# EXP_TMS9918A_V1.net
KiCad netlist of a schematic drawn in EAGLE
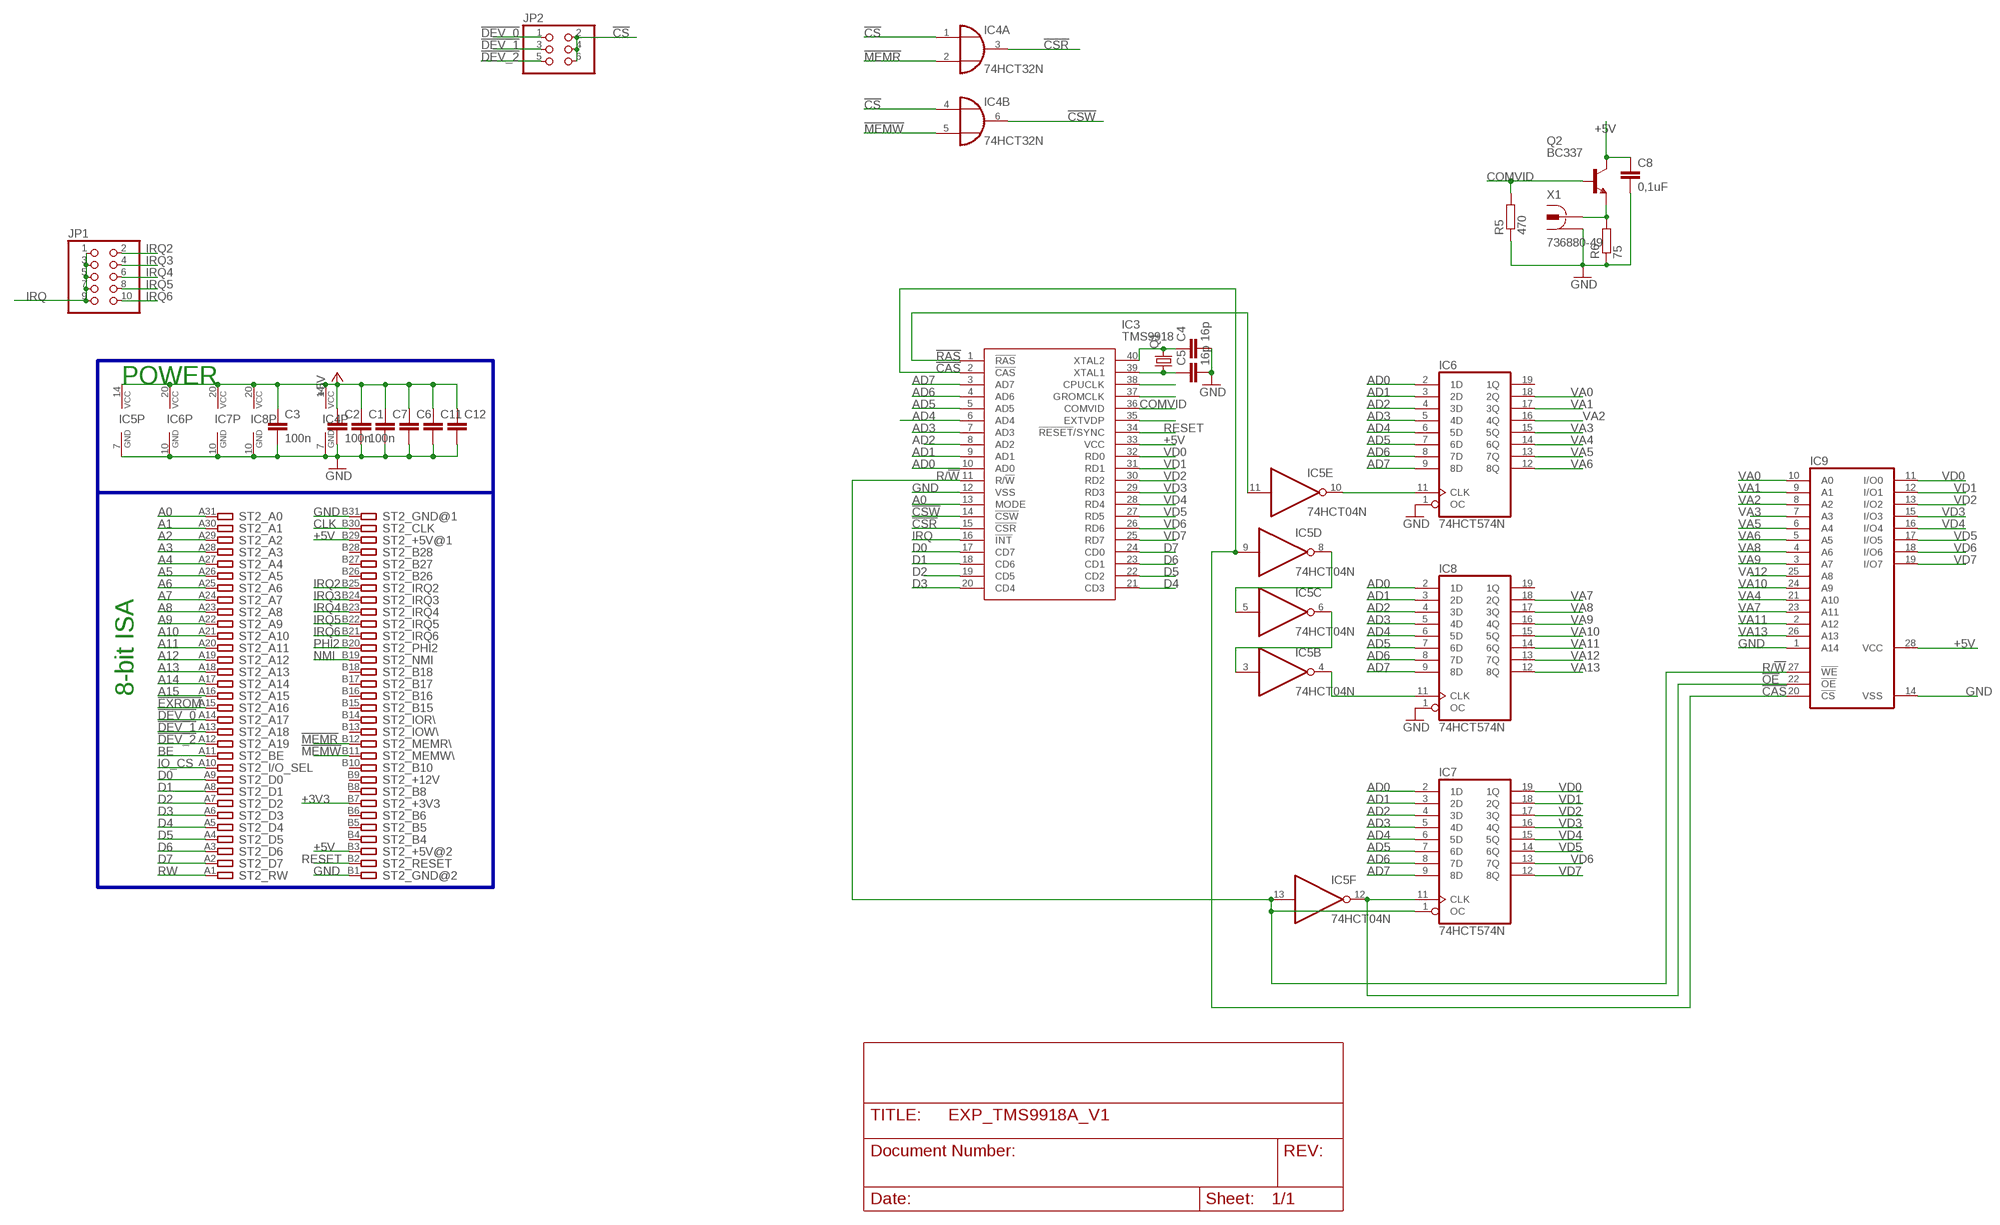
[diagram p0: schematic, sheet 1]

(export (version "E")
  (design (tool "Eeschema 10.0.6"))
  (components
    (comp (ref "C1")
      (value "100n")
      (footprint "eagle-import:C050-025X075")
      (libsource (lib "eagle-import") (part "C-EU050-025X075"))
    )
    (comp (ref "C2")
      (value "100n")
      (footprint "eagle-import:C050-025X075")
      (libsource (lib "eagle-import") (part "C-EU050-025X075"))
    )
    (comp (ref "C3")
      (value "100n")
      (footprint "eagle-import:C050-025X075")
      (libsource (lib "eagle-import") (part "C-EU050-025X075"))
    )
    (comp (ref "C4")
      (value "16p")
      (footprint "eagle-import:C050-024X044")
      (libsource (lib "eagle-import") (part "rcl_334_C-EU050-024X044"))
    )
    (comp (ref "C5")
      (value "16p")
      (footprint "eagle-import:C050-024X044")
      (libsource (lib "eagle-import") (part "rcl_334_C-EU050-024X044"))
    )
    (comp (ref "C6")
      (value "C-EU050-035X075")
      (footprint "eagle-import:C050-035X075")
      (libsource (lib "eagle-import") (part "rcl_334_C-EU050-035X075"))
    )
    (comp (ref "C7")
      (value "C-EU050-035X075")
      (footprint "eagle-import:C050-035X075")
      (libsource (lib "eagle-import") (part "rcl_334_C-EU050-035X075"))
    )
    (comp (ref "C8")
      (value "0,1uF")
      (footprint "eagle-import:C050-024X044")
      (libsource (lib "eagle-import") (part "rcl_334_C-EU050-024X044"))
    )
    (comp (ref "C11")
      (value "C-EU050-035X075")
      (footprint "eagle-import:C050-035X075")
      (libsource (lib "eagle-import") (part "rcl_334_C-EU050-035X075"))
    )
    (comp (ref "C12")
      (value "C-EU050-035X075")
      (footprint "eagle-import:C050-035X075")
      (libsource (lib "eagle-import") (part "rcl_334_C-EU050-035X075"))
    )
    (comp (ref "IC3")
      (value "TMS9918")
      (footprint "eagle-import:DIP1524W53P254L5310H508Q40N")
      (libsource (lib "eagle-import") (part "TMS9918"))
    )
    (comp (ref "IC4")
      (value "74HCT32N")
      (footprint "eagle-import:DIL14")
      (libsource (lib "eagle-import") (part "7432NHCT"))
    )
    (comp (ref "IC5")
      (value "74HCT04N")
      (footprint "eagle-import:DIL14")
      (libsource (lib "eagle-import") (part "7404NHCT"))
    )
    (comp (ref "IC6")
      (value "74HCT574N")
      (footprint "eagle-import:DIL20")
      (libsource (lib "eagle-import") (part "74574NHCT"))
    )
    (comp (ref "IC7")
      (value "74HCT574N")
      (footprint "eagle-import:DIL20")
      (libsource (lib "eagle-import") (part "74574NHCT"))
    )
    (comp (ref "IC8")
      (value "74HCT574N")
      (footprint "eagle-import:DIL20")
      (libsource (lib "eagle-import") (part "74574NHCT"))
    )
    (comp (ref "IC9")
      (value "62256P")
      (footprint "eagle-import:DIL28-6")
      (libsource (lib "eagle-import") (part "62256P"))
    )
    (comp (ref "JP1")
      (value "PINHD-2X5")
      (footprint "eagle-import:2X05")
      (libsource (lib "eagle-import") (part "PINHD-2X5"))
    )
    (comp (ref "JP2")
      (value "PINHD-2X3")
      (footprint "eagle-import:2X03")
      (libsource (lib "eagle-import") (part "PINHD-2X3"))
    )
    (comp (ref "Q1")
      (value "CRYSTALHC49S")
      (footprint "eagle-import:HC49_S")
      (libsource (lib "eagle-import") (part "CRYSTALHC49S"))
    )
    (comp (ref "Q2")
      (value "BC337")
      (footprint "eagle-import:TO92")
      (libsource (lib "eagle-import") (part "BC337"))
    )
    (comp (ref "R5")
      (value "470")
      (footprint "eagle-import:0207_7")
      (libsource (lib "eagle-import") (part "R-EU_0207/7"))
    )
    (comp (ref "R6")
      (value "75")
      (footprint "eagle-import:0207_7")
      (libsource (lib "eagle-import") (part "R-EU_0207/7"))
    )
    (comp (ref "ST2")
      (value "IBM8BIT_ISASHORT")
      (footprint "eagle-import:APP_2X32_SHORT")
      (libsource (lib "eagle-import") (part "IBM8BIT_ISASHORT"))
    )
    (comp (ref "X1")
      (value "736880-49")
      (footprint "eagle-import:736880-49")
      (libsource (lib "eagle-import") (part "736880-49"))
    )
  )
  (nets
    (net (code "1") (name "+5V") (class "Default")
      (node (ref "C1") (pin "1") (pinfunction "1_1") (pintype "passive"))
      (node (ref "C11") (pin "1") (pinfunction "1_1") (pintype "passive"))
      (node (ref "C12") (pin "1") (pinfunction "1_1") (pintype "passive"))
      (node (ref "C2") (pin "1") (pinfunction "1_1") (pintype "passive"))
      (node (ref "C3") (pin "1") (pinfunction "1_1") (pintype "passive"))
      (node (ref "C6") (pin "1") (pinfunction "1_1") (pintype "passive"))
      (node (ref "C7") (pin "1") (pinfunction "1_1") (pintype "passive"))
      (node (ref "C8") (pin "1") (pinfunction "1_1") (pintype "passive"))
      (node (ref "IC3") (pin "33") (pinfunction "VCC_33") (pintype "bidirectional"))
      (node (ref "IC4") (pin "14") (pinfunction "VCC_14") (pintype "power_in"))
      (node (ref "IC5") (pin "14") (pinfunction "VCC_14") (pintype "power_in"))
      (node (ref "IC6") (pin "20") (pinfunction "VCC_20") (pintype "power_in"))
      (node (ref "IC7") (pin "20") (pinfunction "VCC_20") (pintype "power_in"))
      (node (ref "IC8") (pin "20") (pinfunction "VCC_20") (pintype "power_in"))
      (node (ref "IC9") (pin "28") (pinfunction "VCC_28") (pintype "power_in"))
      (node (ref "Q2") (pin "3") (pinfunction "C_3") (pintype "passive"))
      (node (ref "ST2") (pin "B29") (pinfunction "P_B29") (pintype "bidirectional"))
      (node (ref "ST2") (pin "B3") (pinfunction "P_B3") (pintype "bidirectional"))
    )
    (net (code "2") (name "/+3V3") (class "Default")
      (node (ref "ST2") (pin "B7") (pinfunction "P_B7") (pintype "bidirectional"))
    )
    (net (code "3") (name "/A0") (class "Default")
      (node (ref "IC3") (pin "13") (pinfunction "MODE_13") (pintype "bidirectional"))
      (node (ref "ST2") (pin "A31") (pinfunction "P_A31") (pintype "bidirectional"))
    )
    (net (code "4") (name "/A1") (class "Default")
      (node (ref "ST2") (pin "A30") (pinfunction "P_A30") (pintype "bidirectional"))
    )
    (net (code "5") (name "/A2") (class "Default")
      (node (ref "ST2") (pin "A29") (pinfunction "P_A29") (pintype "bidirectional"))
    )
    (net (code "6") (name "/A3") (class "Default")
      (node (ref "ST2") (pin "A28") (pinfunction "P_A28") (pintype "bidirectional"))
    )
    (net (code "7") (name "/A4") (class "Default")
      (node (ref "ST2") (pin "A27") (pinfunction "P_A27") (pintype "bidirectional"))
    )
    (net (code "8") (name "/A5") (class "Default")
      (node (ref "ST2") (pin "A26") (pinfunction "P_A26") (pintype "bidirectional"))
    )
    (net (code "9") (name "/A6") (class "Default")
      (node (ref "ST2") (pin "A25") (pinfunction "P_A25") (pintype "bidirectional"))
    )
    (net (code "10") (name "/A7") (class "Default")
      (node (ref "ST2") (pin "A24") (pinfunction "P_A24") (pintype "bidirectional"))
    )
    (net (code "11") (name "/A8") (class "Default")
      (node (ref "ST2") (pin "A23") (pinfunction "P_A23") (pintype "bidirectional"))
    )
    (net (code "12") (name "/A9") (class "Default")
      (node (ref "ST2") (pin "A22") (pinfunction "P_A22") (pintype "bidirectional"))
    )
    (net (code "13") (name "/A10") (class "Default")
      (node (ref "ST2") (pin "A21") (pinfunction "P_A21") (pintype "bidirectional"))
    )
    (net (code "14") (name "/A11") (class "Default")
      (node (ref "ST2") (pin "A20") (pinfunction "P_A20") (pintype "bidirectional"))
    )
    (net (code "15") (name "/A12") (class "Default")
      (node (ref "ST2") (pin "A19") (pinfunction "P_A19") (pintype "bidirectional"))
    )
    (net (code "16") (name "/A13") (class "Default")
      (node (ref "ST2") (pin "A18") (pinfunction "P_A18") (pintype "bidirectional"))
    )
    (net (code "17") (name "/A14") (class "Default")
      (node (ref "ST2") (pin "A17") (pinfunction "P_A17") (pintype "bidirectional"))
    )
    (net (code "18") (name "/A15") (class "Default")
      (node (ref "ST2") (pin "A16") (pinfunction "P_A16") (pintype "bidirectional"))
    )
    (net (code "19") (name "/AD0") (class "Default")
      (node (ref "IC3") (pin "10") (pinfunction "AD0_10") (pintype "bidirectional"))
      (node (ref "IC6") (pin "2") (pinfunction "1D_2") (pintype "input"))
      (node (ref "IC7") (pin "2") (pinfunction "1D_2") (pintype "input"))
      (node (ref "IC8") (pin "2") (pinfunction "1D_2") (pintype "input"))
    )
    (net (code "20") (name "/AD1") (class "Default")
      (node (ref "IC3") (pin "9") (pinfunction "AD1_9") (pintype "bidirectional"))
      (node (ref "IC6") (pin "3") (pinfunction "2D_3") (pintype "input"))
      (node (ref "IC7") (pin "3") (pinfunction "2D_3") (pintype "input"))
      (node (ref "IC8") (pin "3") (pinfunction "2D_3") (pintype "input"))
    )
    (net (code "21") (name "/AD2") (class "Default")
      (node (ref "IC3") (pin "8") (pinfunction "AD2_8") (pintype "bidirectional"))
      (node (ref "IC6") (pin "4") (pinfunction "3D_4") (pintype "input"))
      (node (ref "IC7") (pin "4") (pinfunction "3D_4") (pintype "input"))
      (node (ref "IC8") (pin "4") (pinfunction "3D_4") (pintype "input"))
    )
    (net (code "22") (name "/AD3") (class "Default")
      (node (ref "IC3") (pin "7") (pinfunction "AD3_7") (pintype "bidirectional"))
      (node (ref "IC6") (pin "5") (pinfunction "4D_5") (pintype "input"))
      (node (ref "IC7") (pin "5") (pinfunction "4D_5") (pintype "input"))
      (node (ref "IC8") (pin "5") (pinfunction "4D_5") (pintype "input"))
    )
    (net (code "23") (name "/AD4") (class "Default")
      (node (ref "IC3") (pin "6") (pinfunction "AD4_6") (pintype "bidirectional"))
      (node (ref "IC6") (pin "6") (pinfunction "5D_6") (pintype "input"))
      (node (ref "IC7") (pin "6") (pinfunction "5D_6") (pintype "input"))
      (node (ref "IC8") (pin "6") (pinfunction "5D_6") (pintype "input"))
    )
    (net (code "24") (name "/AD5") (class "Default")
      (node (ref "IC3") (pin "5") (pinfunction "AD5_5") (pintype "bidirectional"))
      (node (ref "IC6") (pin "7") (pinfunction "6D_7") (pintype "input"))
      (node (ref "IC7") (pin "7") (pinfunction "6D_7") (pintype "input"))
      (node (ref "IC8") (pin "7") (pinfunction "6D_7") (pintype "input"))
    )
    (net (code "25") (name "/AD6") (class "Default")
      (node (ref "IC3") (pin "4") (pinfunction "AD6_4") (pintype "bidirectional"))
      (node (ref "IC6") (pin "8") (pinfunction "7D_8") (pintype "input"))
      (node (ref "IC7") (pin "8") (pinfunction "7D_8") (pintype "input"))
      (node (ref "IC8") (pin "8") (pinfunction "7D_8") (pintype "input"))
    )
    (net (code "26") (name "/AD7") (class "Default")
      (node (ref "IC3") (pin "3") (pinfunction "AD7_3") (pintype "bidirectional"))
      (node (ref "IC6") (pin "9") (pinfunction "8D_9") (pintype "input"))
      (node (ref "IC7") (pin "9") (pinfunction "8D_9") (pintype "input"))
      (node (ref "IC8") (pin "9") (pinfunction "8D_9") (pintype "input"))
    )
    (net (code "27") (name "/BE") (class "Default")
      (node (ref "ST2") (pin "A11") (pinfunction "P_A11") (pintype "bidirectional"))
    )
    (net (code "28") (name "/CLK") (class "Default")
      (node (ref "ST2") (pin "B30") (pinfunction "P_B30") (pintype "bidirectional"))
    )
    (net (code "29") (name "/COMVID") (class "Default")
      (node (ref "IC3") (pin "36") (pinfunction "COMVID_36") (pintype "bidirectional"))
      (node (ref "Q2") (pin "2") (pinfunction "B_2") (pintype "passive"))
      (node (ref "R5") (pin "2") (pinfunction "2_2") (pintype "passive"))
    )
    (net (code "30") (name "/D0") (class "Default")
      (node (ref "IC3") (pin "17") (pinfunction "CD7_17") (pintype "bidirectional"))
      (node (ref "ST2") (pin "A9") (pinfunction "P_A9") (pintype "bidirectional"))
    )
    (net (code "31") (name "/D1") (class "Default")
      (node (ref "IC3") (pin "18") (pinfunction "CD6_18") (pintype "bidirectional"))
      (node (ref "ST2") (pin "A8") (pinfunction "P_A8") (pintype "bidirectional"))
    )
    (net (code "32") (name "/D2") (class "Default")
      (node (ref "IC3") (pin "19") (pinfunction "CD5_19") (pintype "bidirectional"))
      (node (ref "ST2") (pin "A7") (pinfunction "P_A7") (pintype "bidirectional"))
    )
    (net (code "33") (name "/D3") (class "Default")
      (node (ref "IC3") (pin "20") (pinfunction "CD4_20") (pintype "bidirectional"))
      (node (ref "ST2") (pin "A6") (pinfunction "P_A6") (pintype "bidirectional"))
    )
    (net (code "34") (name "/D4") (class "Default")
      (node (ref "IC3") (pin "21") (pinfunction "CD3_21") (pintype "bidirectional"))
      (node (ref "ST2") (pin "A5") (pinfunction "P_A5") (pintype "bidirectional"))
    )
    (net (code "35") (name "/D5") (class "Default")
      (node (ref "IC3") (pin "22") (pinfunction "CD2_22") (pintype "bidirectional"))
      (node (ref "ST2") (pin "A4") (pinfunction "P_A4") (pintype "bidirectional"))
    )
    (net (code "36") (name "/D6") (class "Default")
      (node (ref "IC3") (pin "23") (pinfunction "CD1_23") (pintype "bidirectional"))
      (node (ref "ST2") (pin "A3") (pinfunction "P_A3") (pintype "bidirectional"))
    )
    (net (code "37") (name "/D7") (class "Default")
      (node (ref "IC3") (pin "24") (pinfunction "CD0_24") (pintype "bidirectional"))
      (node (ref "ST2") (pin "A2") (pinfunction "P_A2") (pintype "bidirectional"))
    )
    (net (code "38") (name "/IO_CS") (class "Default")
      (node (ref "ST2") (pin "A10") (pinfunction "P_A10") (pintype "bidirectional"))
    )
    (net (code "39") (name "/IRQ") (class "Default")
      (node (ref "IC3") (pin "16") (pinfunction "~{INT}_16") (pintype "bidirectional"))
      (node (ref "JP1") (pin "1") (pinfunction "1_1") (pintype "passive"))
      (node (ref "JP1") (pin "3") (pinfunction "3_3") (pintype "passive"))
      (node (ref "JP1") (pin "5") (pinfunction "5_5") (pintype "passive"))
      (node (ref "JP1") (pin "7") (pinfunction "7_7") (pintype "passive"))
      (node (ref "JP1") (pin "9") (pinfunction "9_9") (pintype "passive"))
    )
    (net (code "40") (name "/IRQ2") (class "Default")
      (node (ref "JP1") (pin "2") (pinfunction "2_2") (pintype "passive"))
      (node (ref "ST2") (pin "B25") (pinfunction "P_B25") (pintype "bidirectional"))
    )
    (net (code "41") (name "/IRQ3") (class "Default")
      (node (ref "JP1") (pin "4") (pinfunction "4_4") (pintype "passive"))
      (node (ref "ST2") (pin "B24") (pinfunction "P_B24") (pintype "bidirectional"))
    )
    (net (code "42") (name "/IRQ4") (class "Default")
      (node (ref "JP1") (pin "6") (pinfunction "6_6") (pintype "passive"))
      (node (ref "ST2") (pin "B23") (pinfunction "P_B23") (pintype "bidirectional"))
    )
    (net (code "43") (name "/IRQ5") (class "Default")
      (node (ref "JP1") (pin "8") (pinfunction "8_8") (pintype "passive"))
      (node (ref "ST2") (pin "B22") (pinfunction "P_B22") (pintype "bidirectional"))
    )
    (net (code "44") (name "/IRQ6") (class "Default")
      (node (ref "JP1") (pin "10") (pinfunction "10_10") (pintype "passive"))
      (node (ref "ST2") (pin "B21") (pinfunction "P_B21") (pintype "bidirectional"))
    )
    (net (code "45") (name "/NMI") (class "Default")
      (node (ref "ST2") (pin "B19") (pinfunction "P_B19") (pintype "bidirectional"))
    )
    (net (code "46") (name "/PHI2") (class "Default")
      (node (ref "ST2") (pin "B20") (pinfunction "P_B20") (pintype "bidirectional"))
    )
    (net (code "47") (name "/RESET") (class "Default")
      (node (ref "IC3") (pin "34") (pinfunction "~{RESET}/SYNC_34") (pintype "bidirectional"))
      (node (ref "ST2") (pin "B2") (pinfunction "P_B2") (pintype "bidirectional"))
    )
    (net (code "48") (name "/RW") (class "Default")
      (node (ref "ST2") (pin "A1") (pinfunction "P_A1") (pintype "bidirectional"))
    )
    (net (code "49") (name "/R{slash}~{W}") (class "Default")
      (node (ref "IC3") (pin "11") (pinfunction "R/~{W}_11") (pintype "bidirectional"))
      (node (ref "IC5") (pin "13") (pinfunction "I_13") (pintype "input"))
      (node (ref "IC7") (pin "1") (pinfunction "OC_1") (pintype "input"))
      (node (ref "IC9") (pin "27") (pinfunction "~{WE}_27") (pintype "input"))
    )
    (net (code "50") (name "/VA0") (class "Default")
      (node (ref "IC6") (pin "18") (pinfunction "2Q_18") (pintype "tri_state"))
      (node (ref "IC9") (pin "10") (pinfunction "A0_10") (pintype "input"))
    )
    (net (code "51") (name "/VA1") (class "Default")
      (node (ref "IC6") (pin "17") (pinfunction "3Q_17") (pintype "tri_state"))
      (node (ref "IC9") (pin "9") (pinfunction "A1_9") (pintype "input"))
    )
    (net (code "52") (name "/VA2") (class "Default")
      (node (ref "IC6") (pin "16") (pinfunction "4Q_16") (pintype "tri_state"))
      (node (ref "IC9") (pin "8") (pinfunction "A2_8") (pintype "input"))
    )
    (net (code "53") (name "/VA3") (class "Default")
      (node (ref "IC6") (pin "15") (pinfunction "5Q_15") (pintype "tri_state"))
      (node (ref "IC9") (pin "7") (pinfunction "A3_7") (pintype "input"))
    )
    (net (code "54") (name "/VA4") (class "Default")
      (node (ref "IC6") (pin "14") (pinfunction "6Q_14") (pintype "tri_state"))
      (node (ref "IC9") (pin "21") (pinfunction "A10_21") (pintype "input"))
    )
    (net (code "55") (name "/VA5") (class "Default")
      (node (ref "IC6") (pin "13") (pinfunction "7Q_13") (pintype "tri_state"))
      (node (ref "IC9") (pin "6") (pinfunction "A4_6") (pintype "input"))
    )
    (net (code "56") (name "/VA6") (class "Default")
      (node (ref "IC6") (pin "12") (pinfunction "8Q_12") (pintype "tri_state"))
      (node (ref "IC9") (pin "5") (pinfunction "A5_5") (pintype "input"))
    )
    (net (code "57") (name "/VA7") (class "Default")
      (node (ref "IC8") (pin "18") (pinfunction "2Q_18") (pintype "tri_state"))
      (node (ref "IC9") (pin "23") (pinfunction "A11_23") (pintype "input"))
    )
    (net (code "58") (name "/VA8") (class "Default")
      (node (ref "IC8") (pin "17") (pinfunction "3Q_17") (pintype "tri_state"))
      (node (ref "IC9") (pin "4") (pinfunction "A6_4") (pintype "input"))
    )
    (net (code "59") (name "/VA9") (class "Default")
      (node (ref "IC8") (pin "16") (pinfunction "4Q_16") (pintype "tri_state"))
      (node (ref "IC9") (pin "3") (pinfunction "A7_3") (pintype "input"))
    )
    (net (code "60") (name "/VA10") (class "Default")
      (node (ref "IC8") (pin "15") (pinfunction "5Q_15") (pintype "tri_state"))
      (node (ref "IC9") (pin "24") (pinfunction "A9_24") (pintype "input"))
    )
    (net (code "61") (name "/VA11") (class "Default")
      (node (ref "IC8") (pin "14") (pinfunction "6Q_14") (pintype "tri_state"))
      (node (ref "IC9") (pin "2") (pinfunction "A12_2") (pintype "input"))
    )
    (net (code "62") (name "/VA12") (class "Default")
      (node (ref "IC8") (pin "13") (pinfunction "7Q_13") (pintype "tri_state"))
      (node (ref "IC9") (pin "25") (pinfunction "A8_25") (pintype "input"))
    )
    (net (code "63") (name "/VA13") (class "Default")
      (node (ref "IC8") (pin "12") (pinfunction "8Q_12") (pintype "tri_state"))
      (node (ref "IC9") (pin "26") (pinfunction "A13_26") (pintype "input"))
    )
    (net (code "64") (name "/VD0") (class "Default")
      (node (ref "IC3") (pin "32") (pinfunction "RD0_32") (pintype "bidirectional"))
      (node (ref "IC7") (pin "19") (pinfunction "1Q_19") (pintype "tri_state"))
      (node (ref "IC9") (pin "11") (pinfunction "I/O0_11") (pintype "bidirectional"))
    )
    (net (code "65") (name "/VD1") (class "Default")
      (node (ref "IC3") (pin "31") (pinfunction "RD1_31") (pintype "bidirectional"))
      (node (ref "IC7") (pin "18") (pinfunction "2Q_18") (pintype "tri_state"))
      (node (ref "IC9") (pin "12") (pinfunction "I/O1_12") (pintype "bidirectional"))
    )
    (net (code "66") (name "/VD2") (class "Default")
      (node (ref "IC3") (pin "30") (pinfunction "RD2_30") (pintype "bidirectional"))
      (node (ref "IC7") (pin "17") (pinfunction "3Q_17") (pintype "tri_state"))
      (node (ref "IC9") (pin "13") (pinfunction "I/O2_13") (pintype "bidirectional"))
    )
    (net (code "67") (name "/VD3") (class "Default")
      (node (ref "IC3") (pin "29") (pinfunction "RD3_29") (pintype "bidirectional"))
      (node (ref "IC7") (pin "16") (pinfunction "4Q_16") (pintype "tri_state"))
      (node (ref "IC9") (pin "15") (pinfunction "I/O3_15") (pintype "bidirectional"))
    )
    (net (code "68") (name "/VD4") (class "Default")
      (node (ref "IC3") (pin "28") (pinfunction "RD4_28") (pintype "bidirectional"))
      (node (ref "IC7") (pin "15") (pinfunction "5Q_15") (pintype "tri_state"))
      (node (ref "IC9") (pin "16") (pinfunction "I/O4_16") (pintype "bidirectional"))
    )
    (net (code "69") (name "/VD5") (class "Default")
      (node (ref "IC3") (pin "27") (pinfunction "RD5_27") (pintype "bidirectional"))
      (node (ref "IC7") (pin "14") (pinfunction "6Q_14") (pintype "tri_state"))
      (node (ref "IC9") (pin "17") (pinfunction "I/O5_17") (pintype "bidirectional"))
    )
    (net (code "70") (name "/VD6") (class "Default")
      (node (ref "IC3") (pin "26") (pinfunction "RD6_26") (pintype "bidirectional"))
      (node (ref "IC7") (pin "13") (pinfunction "7Q_13") (pintype "tri_state"))
      (node (ref "IC9") (pin "18") (pinfunction "I/O6_18") (pintype "bidirectional"))
    )
    (net (code "71") (name "/VD7") (class "Default")
      (node (ref "IC3") (pin "25") (pinfunction "RD7_25") (pintype "bidirectional"))
      (node (ref "IC7") (pin "12") (pinfunction "8Q_12") (pintype "tri_state"))
      (node (ref "IC9") (pin "19") (pinfunction "I/O7_19") (pintype "bidirectional"))
    )
    (net (code "72") (name "/~{CAS}") (class "Default")
      (node (ref "IC3") (pin "2") (pinfunction "~{CAS}_2") (pintype "bidirectional"))
      (node (ref "IC5") (pin "9") (pinfunction "I_9") (pintype "input"))
      (node (ref "IC9") (pin "20") (pinfunction "~{CS}_20") (pintype "input"))
    )
    (net (code "73") (name "/~{CSR}") (class "Default")
      (node (ref "IC3") (pin "15") (pinfunction "~{CSR}_15") (pintype "bidirectional"))
      (node (ref "IC4") (pin "3") (pinfunction "O_3") (pintype "output"))
    )
    (net (code "74") (name "/~{CSW}") (class "Default")
      (node (ref "IC3") (pin "14") (pinfunction "~{CSW}_14") (pintype "bidirectional"))
      (node (ref "IC4") (pin "6") (pinfunction "O_6") (pintype "output"))
    )
    (net (code "75") (name "/~{CS}") (class "Default")
      (node (ref "IC4") (pin "1") (pinfunction "I0_1") (pintype "input"))
      (node (ref "IC4") (pin "4") (pinfunction "I0_4") (pintype "input"))
      (node (ref "JP2") (pin "2") (pinfunction "2_2") (pintype "passive"))
      (node (ref "JP2") (pin "4") (pinfunction "4_4") (pintype "passive"))
      (node (ref "JP2") (pin "6") (pinfunction "6_6") (pintype "passive"))
    )
    (net (code "76") (name "/~{DEV_0}") (class "Default")
      (node (ref "JP2") (pin "1") (pinfunction "1_1") (pintype "passive"))
      (node (ref "ST2") (pin "A14") (pinfunction "P_A14") (pintype "bidirectional"))
    )
    (net (code "77") (name "/~{DEV_1}") (class "Default")
      (node (ref "JP2") (pin "3") (pinfunction "3_3") (pintype "passive"))
      (node (ref "ST2") (pin "A13") (pinfunction "P_A13") (pintype "bidirectional"))
    )
    (net (code "78") (name "/~{DEV_2}") (class "Default")
      (node (ref "JP2") (pin "5") (pinfunction "5_5") (pintype "passive"))
      (node (ref "ST2") (pin "A12") (pinfunction "P_A12") (pintype "bidirectional"))
    )
    (net (code "79") (name "/~{EXROM}") (class "Default")
      (node (ref "ST2") (pin "A15") (pinfunction "P_A15") (pintype "bidirectional"))
    )
    (net (code "80") (name "/~{MEMR}") (class "Default")
      (node (ref "IC4") (pin "2") (pinfunction "I1_2") (pintype "input"))
      (node (ref "ST2") (pin "B12") (pinfunction "P_B12") (pintype "bidirectional"))
    )
    (net (code "81") (name "/~{MEMW}") (class "Default")
      (node (ref "IC4") (pin "5") (pinfunction "I1_5") (pintype "input"))
      (node (ref "ST2") (pin "B11") (pinfunction "P_B11") (pintype "bidirectional"))
    )
    (net (code "82") (name "/~{OE}") (class "Default")
      (node (ref "IC5") (pin "12") (pinfunction "O_12") (pintype "output"))
      (node (ref "IC7") (pin "11") (pinfunction "CLK_11") (pintype "input"))
      (node (ref "IC9") (pin "22") (pinfunction "~{OE}_22") (pintype "input"))
    )
    (net (code "83") (name "/~{RAS}") (class "Default")
      (node (ref "IC3") (pin "1") (pinfunction "~{RAS}_1") (pintype "bidirectional"))
      (node (ref "IC5") (pin "11") (pinfunction "I_11") (pintype "input"))
    )
    (net (code "84") (name "GND") (class "Default")
      (node (ref "C1") (pin "2") (pinfunction "2_2") (pintype "passive"))
      (node (ref "C11") (pin "2") (pinfunction "2_2") (pintype "passive"))
      (node (ref "C12") (pin "2") (pinfunction "2_2") (pintype "passive"))
      (node (ref "C2") (pin "2") (pinfunction "2_2") (pintype "passive"))
      (node (ref "C3") (pin "2") (pinfunction "2_2") (pintype "passive"))
      (node (ref "C4") (pin "2") (pinfunction "2_2") (pintype "passive"))
      (node (ref "C5") (pin "2") (pinfunction "2_2") (pintype "passive"))
      (node (ref "C6") (pin "2") (pinfunction "2_2") (pintype "passive"))
      (node (ref "C7") (pin "2") (pinfunction "2_2") (pintype "passive"))
      (node (ref "C8") (pin "2") (pinfunction "2_2") (pintype "passive"))
      (node (ref "IC3") (pin "12") (pinfunction "VSS_12") (pintype "bidirectional"))
      (node (ref "IC4") (pin "7") (pinfunction "GND_7") (pintype "power_in"))
      (node (ref "IC5") (pin "7") (pinfunction "GND_7") (pintype "power_in"))
      (node (ref "IC6") (pin "1") (pinfunction "OC_1") (pintype "input"))
      (node (ref "IC6") (pin "10") (pinfunction "GND_10") (pintype "power_in"))
      (node (ref "IC7") (pin "10") (pinfunction "GND_10") (pintype "power_in"))
      (node (ref "IC8") (pin "1") (pinfunction "OC_1") (pintype "input"))
      (node (ref "IC8") (pin "10") (pinfunction "GND_10") (pintype "power_in"))
      (node (ref "IC9") (pin "1") (pinfunction "A14_1") (pintype "input"))
      (node (ref "IC9") (pin "14") (pinfunction "VSS_14") (pintype "power_in"))
      (node (ref "R5") (pin "1") (pinfunction "1_1") (pintype "passive"))
      (node (ref "R6") (pin "1") (pinfunction "1_1") (pintype "passive"))
      (node (ref "ST2") (pin "B1") (pinfunction "P_B1") (pintype "bidirectional"))
      (node (ref "ST2") (pin "B31") (pinfunction "P_B31") (pintype "bidirectional"))
      (node (ref "X1") (pin "1") (pinfunction "1_1") (pintype "passive"))
      (node (ref "X1") (pin "1@1") (pinfunction "1_1@1") (pintype "passive"))
      (node (ref "X1") (pin "1@2") (pinfunction "1_1@2") (pintype "passive"))
    )
    (net (code "85") (name "Net-(IC3-XTAL1)") (class "Default")
      (node (ref "C5") (pin "1") (pinfunction "1_1") (pintype "passive"))
      (node (ref "IC3") (pin "39") (pinfunction "XTAL1_39") (pintype "bidirectional"))
      (node (ref "Q1") (pin "1") (pinfunction "1_1") (pintype "passive"))
    )
    (net (code "86") (name "Net-(IC3-XTAL2)") (class "Default")
      (node (ref "C4") (pin "1") (pinfunction "1_1") (pintype "passive"))
      (node (ref "IC3") (pin "40") (pinfunction "XTAL2_40") (pintype "bidirectional"))
      (node (ref "Q1") (pin "2") (pinfunction "2_2") (pintype "passive"))
    )
    (net (code "87") (name "Net-(IC5B-I)") (class "Default")
      (node (ref "IC5") (pin "3") (pinfunction "I_3") (pintype "input"))
      (node (ref "IC5") (pin "6") (pinfunction "O_6") (pintype "output"))
    )
    (net (code "88") (name "Net-(IC5B-O)") (class "Default")
      (node (ref "IC5") (pin "4") (pinfunction "O_4") (pintype "output"))
      (node (ref "IC8") (pin "11") (pinfunction "CLK_11") (pintype "input"))
    )
    (net (code "89") (name "Net-(IC5C-I)") (class "Default")
      (node (ref "IC5") (pin "5") (pinfunction "I_5") (pintype "input"))
      (node (ref "IC5") (pin "8") (pinfunction "O_8") (pintype "output"))
    )
    (net (code "90") (name "Net-(IC5E-O)") (class "Default")
      (node (ref "IC5") (pin "10") (pinfunction "O_10") (pintype "output"))
      (node (ref "IC6") (pin "11") (pinfunction "CLK_11") (pintype "input"))
    )
    (net (code "91") (name "Net-(Q2-E)") (class "Default")
      (node (ref "Q2") (pin "1") (pinfunction "E_1") (pintype "passive"))
      (node (ref "R6") (pin "2") (pinfunction "2_2") (pintype "passive"))
      (node (ref "X1") (pin "2") (pinfunction "2_2") (pintype "passive"))
    )
    (net (code "92") (name "unconnected-(IC3-CPUCLK-Pad38)") (class "Default")
      (node (ref "IC3") (pin "38") (pinfunction "CPUCLK_38") (pintype "bidirectional"))
    )
    (net (code "93") (name "unconnected-(IC3-EXTVDP-Pad35)") (class "Default")
      (node (ref "IC3") (pin "35") (pinfunction "EXTVDP_35") (pintype "bidirectional"))
    )
    (net (code "94") (name "unconnected-(IC3-GROMCLK-Pad37)") (class "Default")
      (node (ref "IC3") (pin "37") (pinfunction "GROMCLK_37") (pintype "bidirectional"))
    )
    (net (code "95") (name "unconnected-(IC6A-1Q-Pad19)") (class "Default")
      (node (ref "IC6") (pin "19") (pinfunction "1Q_19") (pintype "tri_state"))
    )
    (net (code "96") (name "unconnected-(IC8A-1Q-Pad19)") (class "Default")
      (node (ref "IC8") (pin "19") (pinfunction "1Q_19") (pintype "tri_state"))
    )
    (net (code "97") (name "unconnected-(ST2A-P-PadB9)") (class "Default")
      (node (ref "ST2") (pin "B9") (pinfunction "P_B9") (pintype "bidirectional"))
    )
    (net (code "98") (name "unconnected-(ST2AA-P-PadB16)") (class "Default")
      (node (ref "ST2") (pin "B16") (pinfunction "P_B16") (pintype "bidirectional"))
    )
    (net (code "99") (name "unconnected-(ST2AB-P-PadB17)") (class "Default")
      (node (ref "ST2") (pin "B17") (pinfunction "P_B17") (pintype "bidirectional"))
    )
    (net (code "100") (name "unconnected-(ST2AC-P-PadB18)") (class "Default")
      (node (ref "ST2") (pin "B18") (pinfunction "P_B18") (pintype "bidirectional"))
    )
    (net (code "101") (name "unconnected-(ST2AD-P-PadB26)") (class "Default")
      (node (ref "ST2") (pin "B26") (pinfunction "P_B26") (pintype "bidirectional"))
    )
    (net (code "102") (name "unconnected-(ST2AE-P-PadB27)") (class "Default")
      (node (ref "ST2") (pin "B27") (pinfunction "P_B27") (pintype "bidirectional"))
    )
    (net (code "103") (name "unconnected-(ST2AF-P-PadB28)") (class "Default")
      (node (ref "ST2") (pin "B28") (pinfunction "P_B28") (pintype "bidirectional"))
    )
    (net (code "104") (name "unconnected-(ST2AG-P-PadB4)") (class "Default")
      (node (ref "ST2") (pin "B4") (pinfunction "P_B4") (pintype "bidirectional"))
    )
    (net (code "105") (name "unconnected-(ST2AH-P-PadB5)") (class "Default")
      (node (ref "ST2") (pin "B5") (pinfunction "P_B5") (pintype "bidirectional"))
    )
    (net (code "106") (name "unconnected-(ST2AI-P-PadB6)") (class "Default")
      (node (ref "ST2") (pin "B6") (pinfunction "P_B6") (pintype "bidirectional"))
    )
    (net (code "107") (name "unconnected-(ST2AJ-P-PadB8)") (class "Default")
      (node (ref "ST2") (pin "B8") (pinfunction "P_B8") (pintype "bidirectional"))
    )
    (net (code "108") (name "unconnected-(ST2AX-P-PadB14)") (class "Default")
      (node (ref "ST2") (pin "B14") (pinfunction "P_B14") (pintype "bidirectional"))
    )
    (net (code "109") (name "unconnected-(ST2AY-P-PadB13)") (class "Default")
      (node (ref "ST2") (pin "B13") (pinfunction "P_B13") (pintype "bidirectional"))
    )
    (net (code "110") (name "unconnected-(ST2Y-P-PadB10)") (class "Default")
      (node (ref "ST2") (pin "B10") (pinfunction "P_B10") (pintype "bidirectional"))
    )
    (net (code "111") (name "unconnected-(ST2Z-P-PadB15)") (class "Default")
      (node (ref "ST2") (pin "B15") (pinfunction "P_B15") (pintype "bidirectional"))
    )
  )
)
